# RS232.net
KiCad netlist of a schematic drawn in Altium Designer
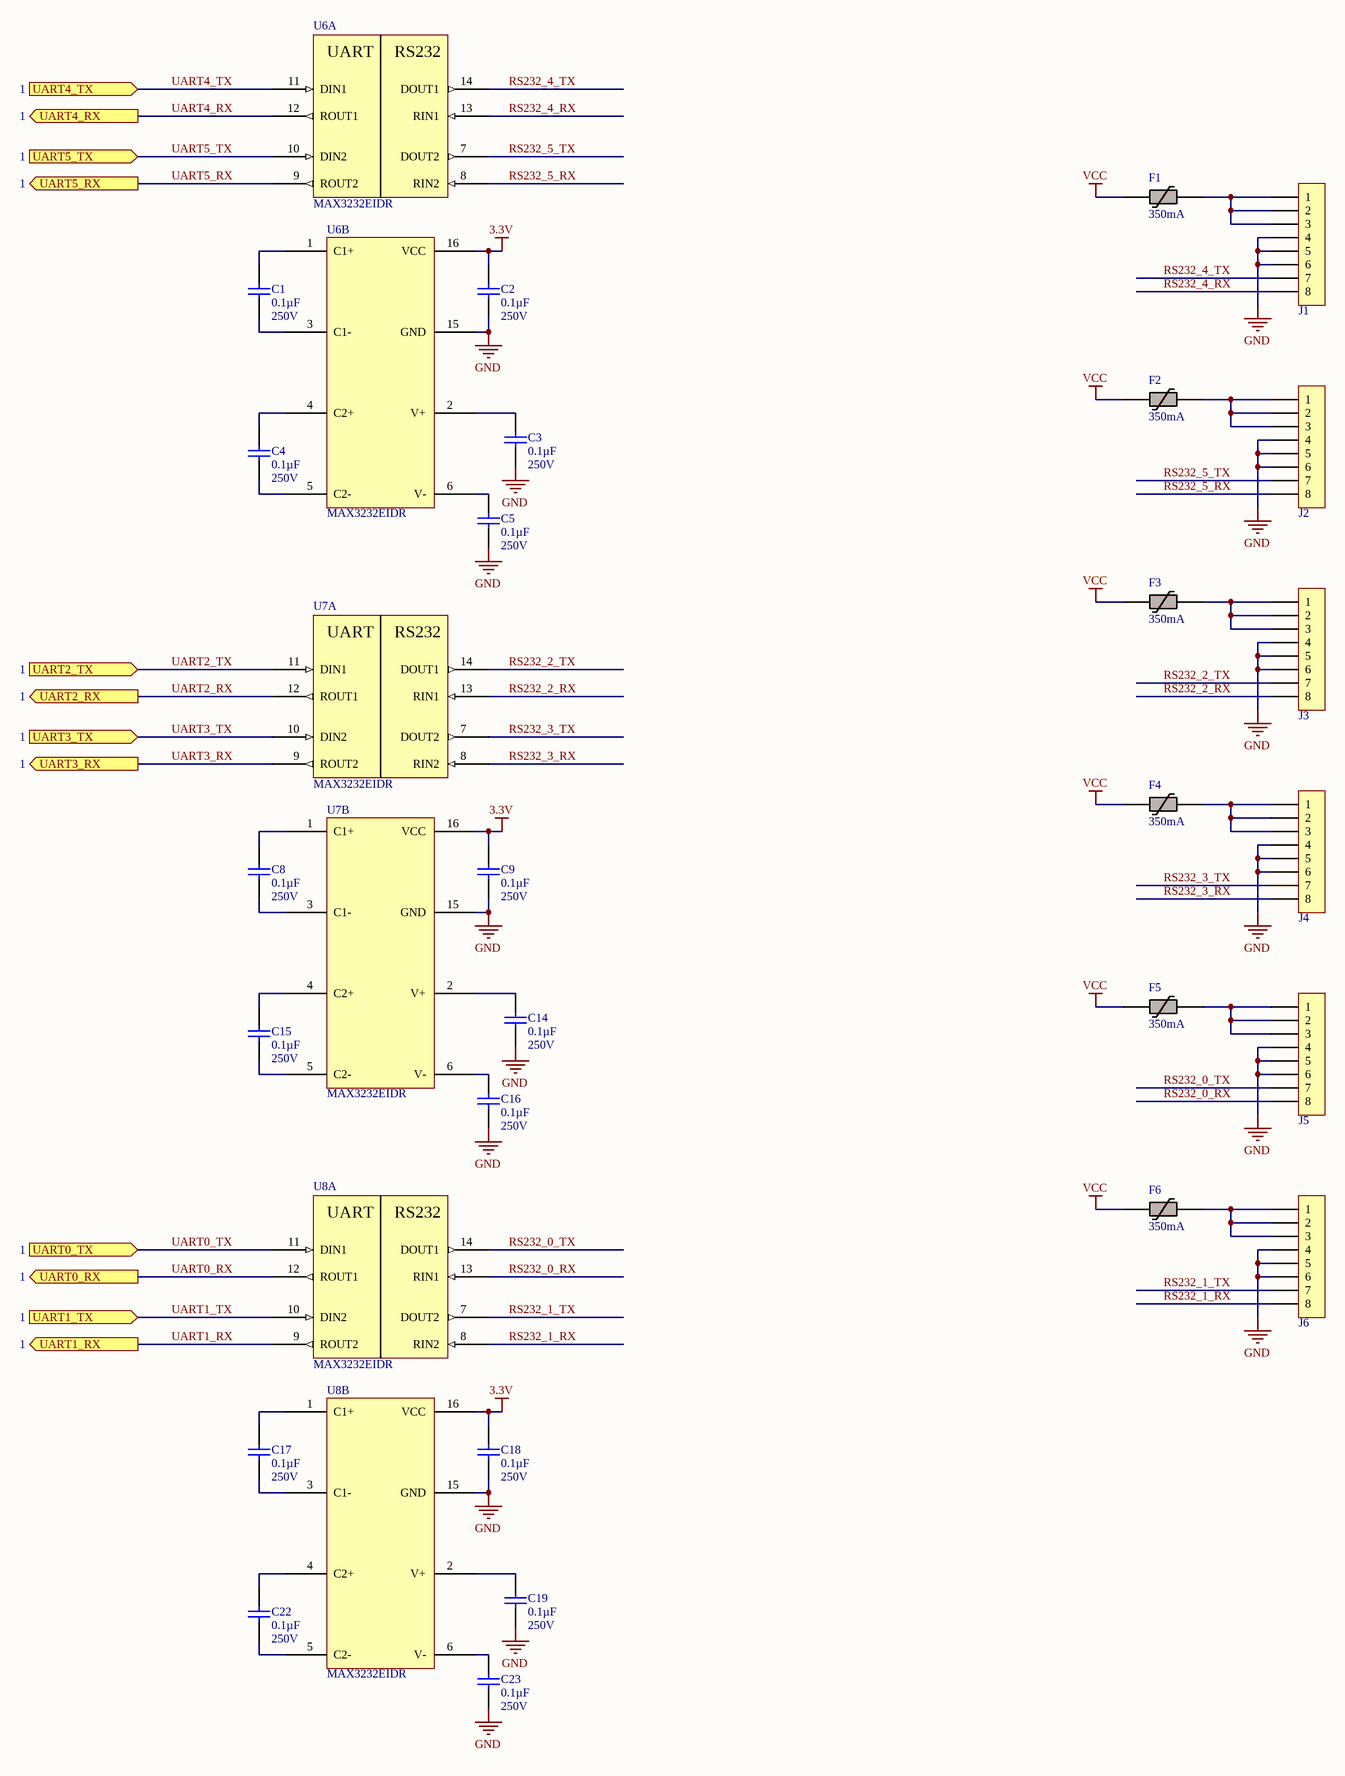
[diagram p0: RS232.SchDoc]

(export (version "E")
  (design (tool "Eeschema 10.0.6"))
  (components
    (comp (ref "C1")
      (value "0.1µF")
      (footprint "Chip0805")
      (description "CAP CER 0.1UF 250V 10% X7T 0805")
      (fields
        (field (name "VOLTAGE") "250V")
        (field (name "PARTNUMBER") "C2012X7T2E104K125AA")
        (field (name "MANUFACTURER") "TDK Corporation")
      )
      (libsource (lib "Passives") (part "CAP"))
    )
    (comp (ref "C2")
      (value "0.1µF")
      (footprint "Chip0805")
      (description "CAP CER 0.1UF 250V 10% X7T 0805")
      (fields
        (field (name "VOLTAGE") "250V")
        (field (name "PARTNUMBER") "C2012X7T2E104K125AA")
        (field (name "MANUFACTURER") "TDK Corporation")
      )
      (libsource (lib "Passives") (part "CAP"))
    )
    (comp (ref "C3")
      (value "0.1µF")
      (footprint "Chip0805")
      (description "CAP CER 0.1UF 250V 10% X7T 0805")
      (fields
        (field (name "VOLTAGE") "250V")
        (field (name "PARTNUMBER") "C2012X7T2E104K125AA")
        (field (name "MANUFACTURER") "TDK Corporation")
      )
      (libsource (lib "Passives") (part "CAP"))
    )
    (comp (ref "C4")
      (value "0.1µF")
      (footprint "Chip0805")
      (description "CAP CER 0.1UF 250V 10% X7T 0805")
      (fields
        (field (name "VOLTAGE") "250V")
        (field (name "PARTNUMBER") "C2012X7T2E104K125AA")
        (field (name "MANUFACTURER") "TDK Corporation")
      )
      (libsource (lib "Passives") (part "CAP"))
    )
    (comp (ref "C5")
      (value "0.1µF")
      (footprint "Chip0805")
      (description "CAP CER 0.1UF 250V 10% X7T 0805")
      (fields
        (field (name "VOLTAGE") "250V")
        (field (name "PARTNUMBER") "C2012X7T2E104K125AA")
        (field (name "MANUFACTURER") "TDK Corporation")
      )
      (libsource (lib "Passives") (part "CAP"))
    )
    (comp (ref "C8")
      (value "0.1µF")
      (footprint "Chip0805")
      (description "CAP CER 0.1UF 250V 10% X7T 0805")
      (fields
        (field (name "VOLTAGE") "250V")
        (field (name "PARTNUMBER") "C2012X7T2E104K125AA")
        (field (name "MANUFACTURER") "TDK Corporation")
      )
      (libsource (lib "Passives") (part "CAP"))
    )
    (comp (ref "C9")
      (value "0.1µF")
      (footprint "Chip0805")
      (description "CAP CER 0.1UF 250V 10% X7T 0805")
      (fields
        (field (name "VOLTAGE") "250V")
        (field (name "PARTNUMBER") "C2012X7T2E104K125AA")
        (field (name "MANUFACTURER") "TDK Corporation")
      )
      (libsource (lib "Passives") (part "CAP"))
    )
    (comp (ref "C14")
      (value "0.1µF")
      (footprint "Chip0805")
      (description "CAP CER 0.1UF 250V 10% X7T 0805")
      (fields
        (field (name "VOLTAGE") "250V")
        (field (name "PARTNUMBER") "C2012X7T2E104K125AA")
        (field (name "MANUFACTURER") "TDK Corporation")
      )
      (libsource (lib "Passives") (part "CAP"))
    )
    (comp (ref "C15")
      (value "0.1µF")
      (footprint "Chip0805")
      (description "CAP CER 0.1UF 250V 10% X7T 0805")
      (fields
        (field (name "VOLTAGE") "250V")
        (field (name "PARTNUMBER") "C2012X7T2E104K125AA")
        (field (name "MANUFACTURER") "TDK Corporation")
      )
      (libsource (lib "Passives") (part "CAP"))
    )
    (comp (ref "C16")
      (value "0.1µF")
      (footprint "Chip0805")
      (description "CAP CER 0.1UF 250V 10% X7T 0805")
      (fields
        (field (name "VOLTAGE") "250V")
        (field (name "PARTNUMBER") "C2012X7T2E104K125AA")
        (field (name "MANUFACTURER") "TDK Corporation")
      )
      (libsource (lib "Passives") (part "CAP"))
    )
    (comp (ref "C17")
      (value "0.1µF")
      (footprint "Chip0805")
      (description "CAP CER 0.1UF 250V 10% X7T 0805")
      (fields
        (field (name "VOLTAGE") "250V")
        (field (name "PARTNUMBER") "C2012X7T2E104K125AA")
        (field (name "MANUFACTURER") "TDK Corporation")
      )
      (libsource (lib "Passives") (part "CAP"))
    )
    (comp (ref "C18")
      (value "0.1µF")
      (footprint "Chip0805")
      (description "CAP CER 0.1UF 250V 10% X7T 0805")
      (fields
        (field (name "VOLTAGE") "250V")
        (field (name "PARTNUMBER") "C2012X7T2E104K125AA")
        (field (name "MANUFACTURER") "TDK Corporation")
      )
      (libsource (lib "Passives") (part "CAP"))
    )
    (comp (ref "C19")
      (value "0.1µF")
      (footprint "Chip0805")
      (description "CAP CER 0.1UF 250V 10% X7T 0805")
      (fields
        (field (name "VOLTAGE") "250V")
        (field (name "PARTNUMBER") "C2012X7T2E104K125AA")
        (field (name "MANUFACTURER") "TDK Corporation")
      )
      (libsource (lib "Passives") (part "CAP"))
    )
    (comp (ref "C22")
      (value "0.1µF")
      (footprint "Chip0805")
      (description "CAP CER 0.1UF 250V 10% X7T 0805")
      (fields
        (field (name "VOLTAGE") "250V")
        (field (name "PARTNUMBER") "C2012X7T2E104K125AA")
        (field (name "MANUFACTURER") "TDK Corporation")
      )
      (libsource (lib "Passives") (part "CAP"))
    )
    (comp (ref "C23")
      (value "0.1µF")
      (footprint "Chip0805")
      (description "CAP CER 0.1UF 250V 10% X7T 0805")
      (fields
        (field (name "VOLTAGE") "250V")
        (field (name "PARTNUMBER") "C2012X7T2E104K125AA")
        (field (name "MANUFACTURER") "TDK Corporation")
      )
      (libsource (lib "Passives") (part "CAP"))
    )
    (comp (ref "F1")
      (value "350mA")
      (footprint "Chip1812")
      (description "PTC RESET FUSE 30V 350MA 1812")
      (fields (field (name "PARTNUMBER") "0ZCG0035AF2C") (field (name "MANUFACTURER") "Bel Fuse Inc."))
      (libsource (lib "Passives") (part "PTC_FUSE"))
    )
    (comp (ref "F2")
      (value "350mA")
      (footprint "Chip1812")
      (description "PTC RESET FUSE 30V 350MA 1812")
      (fields (field (name "PARTNUMBER") "0ZCG0035AF2C") (field (name "MANUFACTURER") "Bel Fuse Inc."))
      (libsource (lib "Passives") (part "PTC_FUSE"))
    )
    (comp (ref "F3")
      (value "350mA")
      (footprint "Chip1812")
      (description "PTC RESET FUSE 30V 350MA 1812")
      (fields (field (name "PARTNUMBER") "0ZCG0035AF2C") (field (name "MANUFACTURER") "Bel Fuse Inc."))
      (libsource (lib "Passives") (part "PTC_FUSE"))
    )
    (comp (ref "F4")
      (value "350mA")
      (footprint "Chip1812")
      (description "PTC RESET FUSE 30V 350MA 1812")
      (fields (field (name "PARTNUMBER") "0ZCG0035AF2C") (field (name "MANUFACTURER") "Bel Fuse Inc."))
      (libsource (lib "Passives") (part "PTC_FUSE"))
    )
    (comp (ref "F5")
      (value "350mA")
      (footprint "Chip1812")
      (description "PTC RESET FUSE 30V 350MA 1812")
      (fields (field (name "PARTNUMBER") "0ZCG0035AF2C") (field (name "MANUFACTURER") "Bel Fuse Inc."))
      (libsource (lib "Passives") (part "PTC_FUSE"))
    )
    (comp (ref "F6")
      (value "350mA")
      (footprint "Chip1812")
      (description "PTC RESET FUSE 30V 350MA 1812")
      (fields (field (name "PARTNUMBER") "0ZCG0035AF2C") (field (name "MANUFACTURER") "Bel Fuse Inc."))
      (libsource (lib "Passives") (part "PTC_FUSE"))
    )
    (comp (ref "J1")
      (value "949")
      (footprint "KEYSTONE_949")
      (description "CONN MOD JACK 8P8C VERT UNSHLD")
      (fields (field (name "MANUFACTURER") "Keystone Electronics"))
      (libsource (lib "Connectors") (part "HEADER_1x8"))
    )
    (comp (ref "J2")
      (value "949")
      (footprint "KEYSTONE_949")
      (description "CONN MOD JACK 8P8C VERT UNSHLD")
      (fields (field (name "MANUFACTURER") "Keystone Electronics"))
      (libsource (lib "Connectors") (part "HEADER_1x8"))
    )
    (comp (ref "J3")
      (value "949")
      (footprint "KEYSTONE_949")
      (description "CONN MOD JACK 8P8C VERT UNSHLD")
      (fields (field (name "MANUFACTURER") "Keystone Electronics"))
      (libsource (lib "Connectors") (part "HEADER_1x8"))
    )
    (comp (ref "J4")
      (value "949")
      (footprint "KEYSTONE_949")
      (description "CONN MOD JACK 8P8C VERT UNSHLD")
      (fields (field (name "MANUFACTURER") "Keystone Electronics"))
      (libsource (lib "Connectors") (part "HEADER_1x8"))
    )
    (comp (ref "J5")
      (value "949")
      (footprint "KEYSTONE_949")
      (description "CONN MOD JACK 8P8C VERT UNSHLD")
      (fields (field (name "MANUFACTURER") "Keystone Electronics"))
      (libsource (lib "Connectors") (part "HEADER_1x8"))
    )
    (comp (ref "J6")
      (value "949")
      (footprint "KEYSTONE_949")
      (description "CONN MOD JACK 8P8C VERT UNSHLD")
      (fields (field (name "MANUFACTURER") "Keystone Electronics"))
      (libsource (lib "Connectors") (part "HEADER_1x8"))
    )
    (comp (ref "U6")
      (value "MAX3232EIDR")
      (footprint "16-SOIC")
      (description "IC TRANSCEIVER FULL 2/2 16SOIC")
      (fields (field (name "MANUFACTURER") "Texas Instruments"))
      (libsource (lib "ICs") (part "TI_MAX3232E"))
    )
    (comp (ref "U7")
      (value "MAX3232EIDR")
      (footprint "16-SOIC")
      (description "IC TRANSCEIVER FULL 2/2 16SOIC")
      (fields (field (name "MANUFACTURER") "Texas Instruments"))
      (libsource (lib "ICs") (part "TI_MAX3232E"))
    )
    (comp (ref "U8")
      (value "MAX3232EIDR")
      (footprint "16-SOIC")
      (description "IC TRANSCEIVER FULL 2/2 16SOIC")
      (fields (field (name "MANUFACTURER") "Texas Instruments"))
      (libsource (lib "ICs") (part "TI_MAX3232E"))
    )
  )
  (nets
    (net (code "1") (name "/RS232_0_RX") (class "Default")
      (node (ref "J5") (pin "8") (pinfunction "8_8") (pintype "passive"))
      (node (ref "U8") (pin "13") (pinfunction "RIN1_13") (pintype "input"))
    )
    (net (code "2") (name "/RS232_0_TX") (class "Default")
      (node (ref "J5") (pin "7") (pinfunction "7_7") (pintype "passive"))
      (node (ref "U8") (pin "14") (pinfunction "DOUT1_14") (pintype "output"))
    )
    (net (code "3") (name "/RS232_1_RX") (class "Default")
      (node (ref "J6") (pin "8") (pinfunction "8_8") (pintype "passive"))
      (node (ref "U8") (pin "8") (pinfunction "RIN2_8") (pintype "input"))
    )
    (net (code "4") (name "/RS232_1_TX") (class "Default")
      (node (ref "J6") (pin "7") (pinfunction "7_7") (pintype "passive"))
      (node (ref "U8") (pin "7") (pinfunction "DOUT2_7") (pintype "output"))
    )
    (net (code "5") (name "/RS232_2_RX") (class "Default")
      (node (ref "J3") (pin "8") (pinfunction "8_8") (pintype "passive"))
      (node (ref "U7") (pin "13") (pinfunction "RIN1_13") (pintype "input"))
    )
    (net (code "6") (name "/RS232_2_TX") (class "Default")
      (node (ref "J3") (pin "7") (pinfunction "7_7") (pintype "passive"))
      (node (ref "U7") (pin "14") (pinfunction "DOUT1_14") (pintype "output"))
    )
    (net (code "7") (name "/RS232_3_RX") (class "Default")
      (node (ref "J4") (pin "8") (pinfunction "8_8") (pintype "passive"))
      (node (ref "U7") (pin "8") (pinfunction "RIN2_8") (pintype "input"))
    )
    (net (code "8") (name "/RS232_3_TX") (class "Default")
      (node (ref "J4") (pin "7") (pinfunction "7_7") (pintype "passive"))
      (node (ref "U7") (pin "7") (pinfunction "DOUT2_7") (pintype "output"))
    )
    (net (code "9") (name "/RS232_4_RX") (class "Default")
      (node (ref "J1") (pin "8") (pinfunction "8_8") (pintype "passive"))
      (node (ref "U6") (pin "13") (pinfunction "RIN1_13") (pintype "input"))
    )
    (net (code "10") (name "/RS232_4_TX") (class "Default")
      (node (ref "J1") (pin "7") (pinfunction "7_7") (pintype "passive"))
      (node (ref "U6") (pin "14") (pinfunction "DOUT1_14") (pintype "output"))
    )
    (net (code "11") (name "/RS232_5_RX") (class "Default")
      (node (ref "J2") (pin "8") (pinfunction "8_8") (pintype "passive"))
      (node (ref "U6") (pin "8") (pinfunction "RIN2_8") (pintype "input"))
    )
    (net (code "12") (name "/RS232_5_TX") (class "Default")
      (node (ref "J2") (pin "7") (pinfunction "7_7") (pintype "passive"))
      (node (ref "U6") (pin "7") (pinfunction "DOUT2_7") (pintype "output"))
    )
    (net (code "13") (name "/UART0_RX") (class "Default")
      (node (ref "U8") (pin "12") (pinfunction "ROUT1_12") (pintype "output"))
    )
    (net (code "14") (name "/UART0_TX") (class "Default")
      (node (ref "U8") (pin "11") (pinfunction "DIN1_11") (pintype "input"))
    )
    (net (code "15") (name "/UART1_RX") (class "Default")
      (node (ref "U8") (pin "9") (pinfunction "ROUT2_9") (pintype "output"))
    )
    (net (code "16") (name "/UART1_TX") (class "Default")
      (node (ref "U8") (pin "10") (pinfunction "DIN2_10") (pintype "input"))
    )
    (net (code "17") (name "/UART2_RX") (class "Default")
      (node (ref "U7") (pin "12") (pinfunction "ROUT1_12") (pintype "output"))
    )
    (net (code "18") (name "/UART2_TX") (class "Default")
      (node (ref "U7") (pin "11") (pinfunction "DIN1_11") (pintype "input"))
    )
    (net (code "19") (name "/UART3_RX") (class "Default")
      (node (ref "U7") (pin "9") (pinfunction "ROUT2_9") (pintype "output"))
    )
    (net (code "20") (name "/UART3_TX") (class "Default")
      (node (ref "U7") (pin "10") (pinfunction "DIN2_10") (pintype "input"))
    )
    (net (code "21") (name "/UART4_RX") (class "Default")
      (node (ref "U6") (pin "12") (pinfunction "ROUT1_12") (pintype "output"))
    )
    (net (code "22") (name "/UART4_TX") (class "Default")
      (node (ref "U6") (pin "11") (pinfunction "DIN1_11") (pintype "input"))
    )
    (net (code "23") (name "/UART5_RX") (class "Default")
      (node (ref "U6") (pin "9") (pinfunction "ROUT2_9") (pintype "output"))
    )
    (net (code "24") (name "/UART5_TX") (class "Default")
      (node (ref "U6") (pin "10") (pinfunction "DIN2_10") (pintype "input"))
    )
    (net (code "25") (name "3.3V") (class "Default")
      (node (ref "C18") (pin "2") (pinfunction "2_2") (pintype "passive"))
      (node (ref "C2") (pin "2") (pinfunction "2_2") (pintype "passive"))
      (node (ref "C9") (pin "2") (pinfunction "2_2") (pintype "passive"))
      (node (ref "U6") (pin "16") (pinfunction "VCC_16") (pintype "passive"))
      (node (ref "U7") (pin "16") (pinfunction "VCC_16") (pintype "passive"))
      (node (ref "U8") (pin "16") (pinfunction "VCC_16") (pintype "passive"))
    )
    (net (code "26") (name "GND") (class "Default")
      (node (ref "C14") (pin "1") (pinfunction "1_1") (pintype "passive"))
      (node (ref "C16") (pin "1") (pinfunction "1_1") (pintype "passive"))
      (node (ref "C18") (pin "1") (pinfunction "1_1") (pintype "passive"))
      (node (ref "C19") (pin "1") (pinfunction "1_1") (pintype "passive"))
      (node (ref "C2") (pin "1") (pinfunction "1_1") (pintype "passive"))
      (node (ref "C23") (pin "1") (pinfunction "1_1") (pintype "passive"))
      (node (ref "C3") (pin "1") (pinfunction "1_1") (pintype "passive"))
      (node (ref "C5") (pin "1") (pinfunction "1_1") (pintype "passive"))
      (node (ref "C9") (pin "1") (pinfunction "1_1") (pintype "passive"))
      (node (ref "J1") (pin "4") (pinfunction "4_4") (pintype "passive"))
      (node (ref "J1") (pin "5") (pinfunction "5_5") (pintype "passive"))
      (node (ref "J1") (pin "6") (pinfunction "6_6") (pintype "passive"))
      (node (ref "J2") (pin "4") (pinfunction "4_4") (pintype "passive"))
      (node (ref "J2") (pin "5") (pinfunction "5_5") (pintype "passive"))
      (node (ref "J2") (pin "6") (pinfunction "6_6") (pintype "passive"))
      (node (ref "J3") (pin "4") (pinfunction "4_4") (pintype "passive"))
      (node (ref "J3") (pin "5") (pinfunction "5_5") (pintype "passive"))
      (node (ref "J3") (pin "6") (pinfunction "6_6") (pintype "passive"))
      (node (ref "J4") (pin "4") (pinfunction "4_4") (pintype "passive"))
      (node (ref "J4") (pin "5") (pinfunction "5_5") (pintype "passive"))
      (node (ref "J4") (pin "6") (pinfunction "6_6") (pintype "passive"))
      (node (ref "J5") (pin "4") (pinfunction "4_4") (pintype "passive"))
      (node (ref "J5") (pin "5") (pinfunction "5_5") (pintype "passive"))
      (node (ref "J5") (pin "6") (pinfunction "6_6") (pintype "passive"))
      (node (ref "J6") (pin "4") (pinfunction "4_4") (pintype "passive"))
      (node (ref "J6") (pin "5") (pinfunction "5_5") (pintype "passive"))
      (node (ref "J6") (pin "6") (pinfunction "6_6") (pintype "passive"))
      (node (ref "U6") (pin "15") (pinfunction "GND_15") (pintype "passive"))
      (node (ref "U7") (pin "15") (pinfunction "GND_15") (pintype "passive"))
      (node (ref "U8") (pin "15") (pinfunction "GND_15") (pintype "passive"))
    )
    (net (code "27") (name "Net-(F1-Pad2)") (class "Default")
      (node (ref "F1") (pin "2") (pinfunction "2_2") (pintype "passive"))
      (node (ref "J1") (pin "1") (pinfunction "1_1") (pintype "passive"))
      (node (ref "J1") (pin "2") (pinfunction "2_2") (pintype "passive"))
      (node (ref "J1") (pin "3") (pinfunction "3_3") (pintype "passive"))
    )
    (net (code "28") (name "Net-(F2-Pad2)") (class "Default")
      (node (ref "F2") (pin "2") (pinfunction "2_2") (pintype "passive"))
      (node (ref "J2") (pin "1") (pinfunction "1_1") (pintype "passive"))
      (node (ref "J2") (pin "2") (pinfunction "2_2") (pintype "passive"))
      (node (ref "J2") (pin "3") (pinfunction "3_3") (pintype "passive"))
    )
    (net (code "29") (name "Net-(F3-Pad2)") (class "Default")
      (node (ref "F3") (pin "2") (pinfunction "2_2") (pintype "passive"))
      (node (ref "J3") (pin "1") (pinfunction "1_1") (pintype "passive"))
      (node (ref "J3") (pin "2") (pinfunction "2_2") (pintype "passive"))
      (node (ref "J3") (pin "3") (pinfunction "3_3") (pintype "passive"))
    )
    (net (code "30") (name "Net-(F4-Pad2)") (class "Default")
      (node (ref "F4") (pin "2") (pinfunction "2_2") (pintype "passive"))
      (node (ref "J4") (pin "1") (pinfunction "1_1") (pintype "passive"))
      (node (ref "J4") (pin "2") (pinfunction "2_2") (pintype "passive"))
      (node (ref "J4") (pin "3") (pinfunction "3_3") (pintype "passive"))
    )
    (net (code "31") (name "Net-(F5-Pad2)") (class "Default")
      (node (ref "F5") (pin "2") (pinfunction "2_2") (pintype "passive"))
      (node (ref "J5") (pin "1") (pinfunction "1_1") (pintype "passive"))
      (node (ref "J5") (pin "2") (pinfunction "2_2") (pintype "passive"))
      (node (ref "J5") (pin "3") (pinfunction "3_3") (pintype "passive"))
    )
    (net (code "32") (name "Net-(F6-Pad2)") (class "Default")
      (node (ref "F6") (pin "2") (pinfunction "2_2") (pintype "passive"))
      (node (ref "J6") (pin "1") (pinfunction "1_1") (pintype "passive"))
      (node (ref "J6") (pin "2") (pinfunction "2_2") (pintype "passive"))
      (node (ref "J6") (pin "3") (pinfunction "3_3") (pintype "passive"))
    )
    (net (code "33") (name "Net-(U6B-C1+)") (class "Default")
      (node (ref "C1") (pin "2") (pinfunction "2_2") (pintype "passive"))
      (node (ref "U6") (pin "1") (pinfunction "C1+_1") (pintype "passive"))
    )
    (net (code "34") (name "Net-(U6B-C1-)") (class "Default")
      (node (ref "C1") (pin "1") (pinfunction "1_1") (pintype "passive"))
      (node (ref "U6") (pin "3") (pinfunction "C1-_3") (pintype "passive"))
    )
    (net (code "35") (name "Net-(U6B-C2+)") (class "Default")
      (node (ref "C4") (pin "2") (pinfunction "2_2") (pintype "passive"))
      (node (ref "U6") (pin "4") (pinfunction "C2+_4") (pintype "passive"))
    )
    (net (code "36") (name "Net-(U6B-C2-)") (class "Default")
      (node (ref "C4") (pin "1") (pinfunction "1_1") (pintype "passive"))
      (node (ref "U6") (pin "5") (pinfunction "C2-_5") (pintype "passive"))
    )
    (net (code "37") (name "Net-(U6B-V+)") (class "Default")
      (node (ref "C3") (pin "2") (pinfunction "2_2") (pintype "passive"))
      (node (ref "U6") (pin "2") (pinfunction "V+_2") (pintype "passive"))
    )
    (net (code "38") (name "Net-(U6B-V-)") (class "Default")
      (node (ref "C5") (pin "2") (pinfunction "2_2") (pintype "passive"))
      (node (ref "U6") (pin "6") (pinfunction "V-_6") (pintype "passive"))
    )
    (net (code "39") (name "Net-(U7B-C1+)") (class "Default")
      (node (ref "C8") (pin "2") (pinfunction "2_2") (pintype "passive"))
      (node (ref "U7") (pin "1") (pinfunction "C1+_1") (pintype "passive"))
    )
    (net (code "40") (name "Net-(U7B-C1-)") (class "Default")
      (node (ref "C8") (pin "1") (pinfunction "1_1") (pintype "passive"))
      (node (ref "U7") (pin "3") (pinfunction "C1-_3") (pintype "passive"))
    )
    (net (code "41") (name "Net-(U7B-C2+)") (class "Default")
      (node (ref "C15") (pin "2") (pinfunction "2_2") (pintype "passive"))
      (node (ref "U7") (pin "4") (pinfunction "C2+_4") (pintype "passive"))
    )
    (net (code "42") (name "Net-(U7B-C2-)") (class "Default")
      (node (ref "C15") (pin "1") (pinfunction "1_1") (pintype "passive"))
      (node (ref "U7") (pin "5") (pinfunction "C2-_5") (pintype "passive"))
    )
    (net (code "43") (name "Net-(U7B-V+)") (class "Default")
      (node (ref "C14") (pin "2") (pinfunction "2_2") (pintype "passive"))
      (node (ref "U7") (pin "2") (pinfunction "V+_2") (pintype "passive"))
    )
    (net (code "44") (name "Net-(U7B-V-)") (class "Default")
      (node (ref "C16") (pin "2") (pinfunction "2_2") (pintype "passive"))
      (node (ref "U7") (pin "6") (pinfunction "V-_6") (pintype "passive"))
    )
    (net (code "45") (name "Net-(U8B-C1+)") (class "Default")
      (node (ref "C17") (pin "2") (pinfunction "2_2") (pintype "passive"))
      (node (ref "U8") (pin "1") (pinfunction "C1+_1") (pintype "passive"))
    )
    (net (code "46") (name "Net-(U8B-C1-)") (class "Default")
      (node (ref "C17") (pin "1") (pinfunction "1_1") (pintype "passive"))
      (node (ref "U8") (pin "3") (pinfunction "C1-_3") (pintype "passive"))
    )
    (net (code "47") (name "Net-(U8B-C2+)") (class "Default")
      (node (ref "C22") (pin "2") (pinfunction "2_2") (pintype "passive"))
      (node (ref "U8") (pin "4") (pinfunction "C2+_4") (pintype "passive"))
    )
    (net (code "48") (name "Net-(U8B-C2-)") (class "Default")
      (node (ref "C22") (pin "1") (pinfunction "1_1") (pintype "passive"))
      (node (ref "U8") (pin "5") (pinfunction "C2-_5") (pintype "passive"))
    )
    (net (code "49") (name "Net-(U8B-V+)") (class "Default")
      (node (ref "C19") (pin "2") (pinfunction "2_2") (pintype "passive"))
      (node (ref "U8") (pin "2") (pinfunction "V+_2") (pintype "passive"))
    )
    (net (code "50") (name "Net-(U8B-V-)") (class "Default")
      (node (ref "C23") (pin "2") (pinfunction "2_2") (pintype "passive"))
      (node (ref "U8") (pin "6") (pinfunction "V-_6") (pintype "passive"))
    )
    (net (code "51") (name "VCC") (class "Default")
      (node (ref "F1") (pin "1") (pinfunction "1_1") (pintype "passive"))
      (node (ref "F2") (pin "1") (pinfunction "1_1") (pintype "passive"))
      (node (ref "F3") (pin "1") (pinfunction "1_1") (pintype "passive"))
      (node (ref "F4") (pin "1") (pinfunction "1_1") (pintype "passive"))
      (node (ref "F5") (pin "1") (pinfunction "1_1") (pintype "passive"))
      (node (ref "F6") (pin "1") (pinfunction "1_1") (pintype "passive"))
    )
  )
)
